# Sheet1.net
KiCad netlist of a schematic drawn in Altium Designer
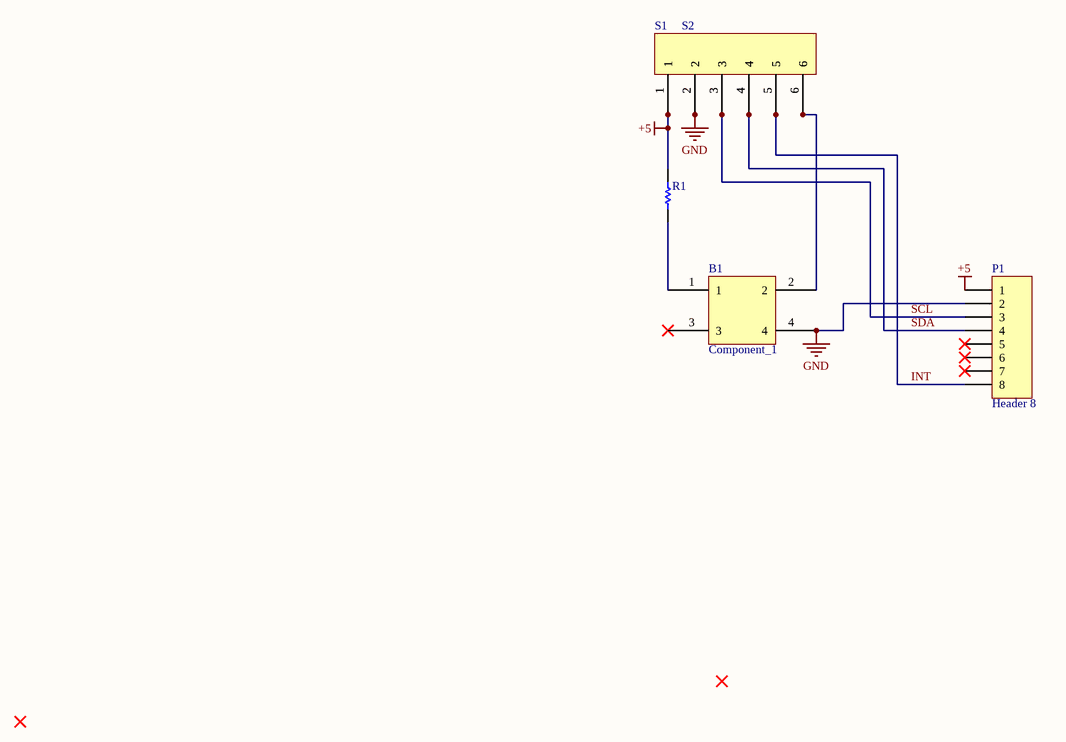
[diagram p0: Sheet1.SchDoc]

(export (version "E")
  (design (tool "Eeschema 10.0.6"))
  (components
    (comp (ref "B1")
      (value "Component_1")
      (footprint "PCBComponent_1")
      (libsource (lib "button") (part "Component_1"))
    )
    (comp (ref "P1")
      (value "Header 8")
      (footprint "HDR1X8")
      (description "Header, 8-Pin")
      (fields (field (name "PUBLISHER") "Altium Limited"))
      (libsource (lib "Miscellaneous Connectors") (part "Header 8"))
    )
    (comp (ref "R1")
      (value "~")
      (footprint "OMTE-RES7X2.5-2")
      (fields
        (field (name "TOLERANCE") "±5%")
        (field (name "PARTNUMBER") "OD103JE")
        (field (name "MANUFACTURER") "Ohmite")
      )
      (libsource (lib "Altium Content Vault") (part "RES-2"))
    )
    (comp (ref "S1")
      (value "~")
      (footprint "PCBComponent_1")
      (libsource (lib "solder_pads") (part "Component_1"))
    )
    (comp (ref "S2")
      (value "~")
      (footprint "PCBComponent_1")
      (libsource (lib "solder_pads") (part "Component_1"))
    )
  )
  (nets
    (net (code "1") (name "+5") (class "Default")
      (node (ref "P1") (pin "1") (pinfunction "1_1") (pintype "passive"))
      (node (ref "R1") (pin "2") (pinfunction "2_2") (pintype "passive"))
      (node (ref "S1") (pin "1") (pinfunction "1_1") (pintype "passive"))
      (node (ref "S2") (pin "1") (pinfunction "1_1") (pintype "passive"))
    )
    (net (code "2") (name "/INT") (class "Default")
      (node (ref "P1") (pin "8") (pinfunction "8_8") (pintype "passive"))
      (node (ref "S1") (pin "5") (pinfunction "5_5") (pintype "passive"))
      (node (ref "S2") (pin "5") (pinfunction "5_5") (pintype "passive"))
    )
    (net (code "3") (name "/SCL") (class "Default")
      (node (ref "P1") (pin "3") (pinfunction "3_3") (pintype "passive"))
      (node (ref "S1") (pin "3") (pinfunction "3_3") (pintype "passive"))
      (node (ref "S2") (pin "3") (pinfunction "3_3") (pintype "passive"))
    )
    (net (code "4") (name "/SDA") (class "Default")
      (node (ref "P1") (pin "4") (pinfunction "4_4") (pintype "passive"))
      (node (ref "S1") (pin "4") (pinfunction "4_4") (pintype "passive"))
      (node (ref "S2") (pin "4") (pinfunction "4_4") (pintype "passive"))
    )
    (net (code "5") (name "GND") (class "Default")
      (node (ref "B1") (pin "4") (pinfunction "4_4") (pintype "passive"))
      (node (ref "P1") (pin "2") (pinfunction "2_2") (pintype "passive"))
      (node (ref "S1") (pin "2") (pinfunction "2_2") (pintype "passive"))
      (node (ref "S2") (pin "2") (pinfunction "2_2") (pintype "passive"))
    )
    (net (code "6") (name "Net-(B1-Pad1)") (class "Default")
      (node (ref "B1") (pin "1") (pinfunction "1_1") (pintype "passive"))
      (node (ref "R1") (pin "1") (pinfunction "1_1") (pintype "passive"))
    )
    (net (code "7") (name "Net-(B1-Pad2)") (class "Default")
      (node (ref "B1") (pin "2") (pinfunction "2_2") (pintype "passive"))
      (node (ref "S1") (pin "6") (pinfunction "6_6") (pintype "passive"))
      (node (ref "S2") (pin "6") (pinfunction "6_6") (pintype "passive"))
    )
    (net (code "8") (name "unconnected-(B1-Pad3)") (class "Default")
      (node (ref "B1") (pin "3") (pinfunction "3_3") (pintype "passive+no_connect"))
    )
    (net (code "9") (name "unconnected-(P1-Pad5)") (class "Default")
      (node (ref "P1") (pin "5") (pinfunction "5_5") (pintype "passive+no_connect"))
    )
    (net (code "10") (name "unconnected-(P1-Pad6)") (class "Default")
      (node (ref "P1") (pin "6") (pinfunction "6_6") (pintype "passive+no_connect"))
    )
    (net (code "11") (name "unconnected-(P1-Pad7)") (class "Default")
      (node (ref "P1") (pin "7") (pinfunction "7_7") (pintype "passive+no_connect"))
    )
  )
)
